# HeadSheet.net
KiCad netlist of a schematic drawn in Altium Designer
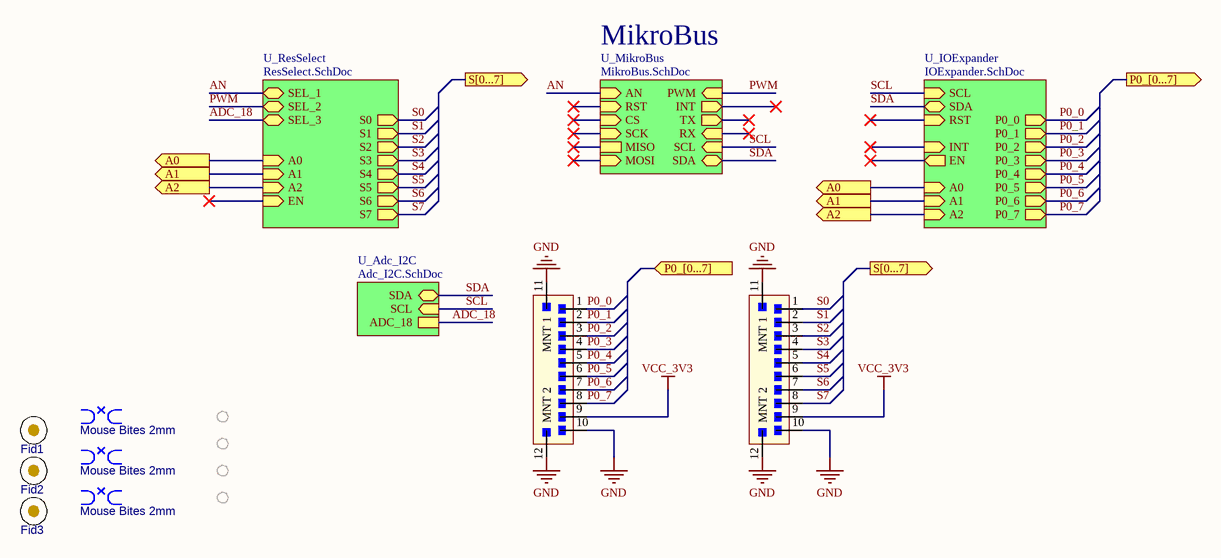
[diagram p0: HeadSheet.SchDoc]

(export (version "E")
  (design (tool "Eeschema 10.0.6"))
  (components
    (comp (ref "BRK1")
      (value "Mouse Bites 2mm")
      (footprint "BK_CRACK1B_M")
      (description "Mouse Bites")
      (fields (field (name "Comment") "DNP"))
      (libsource (lib "TEP-AltiumLib-Hardware") (part "BK_BREAKOUT_2MM"))
    )
    (comp (ref "BRK2")
      (value "Mouse Bites 2mm")
      (footprint "BK_CRACK1B_M")
      (description "Mouse Bites")
      (fields (field (name "Comment") "DNP"))
      (libsource (lib "TEP-AltiumLib-Hardware") (part "BK_BREAKOUT_2MM"))
    )
    (comp (ref "BRK3")
      (value "Mouse Bites 2mm")
      (footprint "BK_CRACK1B_M")
      (description "Mouse Bites")
      (fields (field (name "Comment") "DNP"))
      (libsource (lib "TEP-AltiumLib-Hardware") (part "BK_BREAKOUT_2MM"))
    )
    (comp (ref "Fid1")
      (value "DNP")
      (footprint "FD_Fiducial")
      (description "Fiducial mark for alignement and Pick&Place")
      (libsource (lib "TEP-AltiumLib-Hardware") (part "Fiducial"))
    )
    (comp (ref "Fid2")
      (value "DNP")
      (footprint "FD_Fiducial")
      (description "Fiducial mark for alignement and Pick&Place")
      (libsource (lib "TEP-AltiumLib-Hardware") (part "Fiducial"))
    )
    (comp (ref "Fid3")
      (value "DNP")
      (footprint "FD_Fiducial")
      (description "Fiducial mark for alignement and Pick&Place")
      (libsource (lib "TEP-AltiumLib-Hardware") (part "Fiducial"))
    )
    (comp (ref "J1")
      (value "HC-ZH-10PWT")
      (footprint "J_S10B-ZR-SM4")
      (description "CONN wire to board SMT R/A 10POS 1.5mm")
      (libsource (lib "TEP-AltiumLib-Connectors") (part "CONN-1MM5-01X10-S10B-H-SMT"))
    )
    (comp (ref "J2")
      (value "HC-ZH-10PWT")
      (footprint "J_S10B-ZR-SM4")
      (description "CONN wire to board SMT R/A 10POS 1.5mm")
      (libsource (lib "TEP-AltiumLib-Connectors") (part "CONN-1MM5-01X10-S10B-H-SMT"))
    )
    (comp (ref "MH1")
      (value "DNP")
      (footprint "MP_M-Hole_M2-NonPlated")
      (description "Mounting Hole 2mm non plated")
      (libsource (lib "TEP-AltiumLib-Hardware") (part "MH-2MM_NP"))
    )
    (comp (ref "MH2")
      (value "DNP")
      (footprint "MP_M-Hole_M2-NonPlated")
      (description "Mounting Hole 2mm non plated")
      (libsource (lib "TEP-AltiumLib-Hardware") (part "MH-2MM_NP"))
    )
    (comp (ref "MH3")
      (value "DNP")
      (footprint "MP_M-Hole_M2-NonPlated")
      (description "Mounting Hole 2mm non plated")
      (libsource (lib "TEP-AltiumLib-Hardware") (part "MH-2MM_NP"))
    )
    (comp (ref "MH4")
      (value "DNP")
      (footprint "MP_M-Hole_M2-NonPlated")
      (description "Mounting Hole 2mm non plated")
      (libsource (lib "TEP-AltiumLib-Hardware") (part "MH-2MM_NP"))
    )
  )
  (nets
    (net (code "14") (name "/P0_0") (class "Default")
      (node (ref "J1") (pin "1") (pinfunction "1_1") (pintype "passive"))
    )
    (net (code "15") (name "/P0_1") (class "Default")
      (node (ref "J1") (pin "2") (pinfunction "2_2") (pintype "passive"))
    )
    (net (code "16") (name "/P0_2") (class "Default")
      (node (ref "J1") (pin "3") (pinfunction "3_3") (pintype "passive"))
    )
    (net (code "17") (name "/P0_3") (class "Default")
      (node (ref "J1") (pin "4") (pinfunction "4_4") (pintype "passive"))
    )
    (net (code "18") (name "/P0_4") (class "Default")
      (node (ref "J1") (pin "5") (pinfunction "5_5") (pintype "passive"))
    )
    (net (code "19") (name "/P0_5") (class "Default")
      (node (ref "J1") (pin "6") (pinfunction "6_6") (pintype "passive"))
    )
    (net (code "20") (name "/P0_6") (class "Default")
      (node (ref "J1") (pin "7") (pinfunction "7_7") (pintype "passive"))
    )
    (net (code "21") (name "/P0_7") (class "Default")
      (node (ref "J1") (pin "8") (pinfunction "8_8") (pintype "passive"))
    )
    (net (code "26") (name "/S0") (class "Default")
      (node (ref "J2") (pin "1") (pinfunction "1_1") (pintype "passive"))
    )
    (net (code "27") (name "/S1") (class "Default")
      (node (ref "J2") (pin "2") (pinfunction "2_2") (pintype "passive"))
    )
    (net (code "28") (name "/S2") (class "Default")
      (node (ref "J2") (pin "3") (pinfunction "3_3") (pintype "passive"))
    )
    (net (code "29") (name "/S3") (class "Default")
      (node (ref "J2") (pin "4") (pinfunction "4_4") (pintype "passive"))
    )
    (net (code "30") (name "/S4") (class "Default")
      (node (ref "J2") (pin "5") (pinfunction "5_5") (pintype "passive"))
    )
    (net (code "31") (name "/S5") (class "Default")
      (node (ref "J2") (pin "6") (pinfunction "6_6") (pintype "passive"))
    )
    (net (code "32") (name "/S6") (class "Default")
      (node (ref "J2") (pin "7") (pinfunction "7_7") (pintype "passive"))
    )
    (net (code "33") (name "/S7") (class "Default")
      (node (ref "J2") (pin "8") (pinfunction "8_8") (pintype "passive"))
    )
    (net (code "39") (name "GND") (class "Default")
      (node (ref "J1") (pin "10") (pinfunction "10_10") (pintype "passive"))
      (node (ref "J1") (pin "11") (pinfunction "MNT_1_11") (pintype "passive"))
      (node (ref "J1") (pin "12") (pinfunction "MNT_2_12") (pintype "passive"))
      (node (ref "J2") (pin "10") (pinfunction "10_10") (pintype "passive"))
      (node (ref "J2") (pin "11") (pinfunction "MNT_1_11") (pintype "passive"))
      (node (ref "J2") (pin "12") (pinfunction "MNT_2_12") (pintype "passive"))
    )
    (net (code "40") (name "VCC_3V3") (class "Default")
      (node (ref "J1") (pin "9") (pinfunction "9_9") (pintype "passive"))
      (node (ref "J2") (pin "9") (pinfunction "9_9") (pintype "passive"))
    )
    (net (code "41") (name "unconnected-(BRK1-Pad1)") (class "Default")
      (node (ref "BRK1") (pin "1") (pinfunction "1_1") (pintype "passive"))
    )
    (net (code "42") (name "unconnected-(BRK1-Pad2)") (class "Default")
      (node (ref "BRK1") (pin "2") (pinfunction "2_2") (pintype "passive"))
    )
    (net (code "43") (name "unconnected-(BRK1-Pad3)") (class "Default")
      (node (ref "BRK1") (pin "3") (pinfunction "3_3") (pintype "passive"))
    )
    (net (code "44") (name "unconnected-(BRK1-Pad4)") (class "Default")
      (node (ref "BRK1") (pin "4") (pinfunction "4_4") (pintype "passive"))
    )
    (net (code "45") (name "unconnected-(BRK1-Pad5)") (class "Default")
      (node (ref "BRK1") (pin "5") (pinfunction "5_5") (pintype "passive"))
    )
    (net (code "46") (name "unconnected-(BRK2-Pad1)") (class "Default")
      (node (ref "BRK2") (pin "1") (pinfunction "1_1") (pintype "passive"))
    )
    (net (code "47") (name "unconnected-(BRK2-Pad2)") (class "Default")
      (node (ref "BRK2") (pin "2") (pinfunction "2_2") (pintype "passive"))
    )
    (net (code "48") (name "unconnected-(BRK2-Pad3)") (class "Default")
      (node (ref "BRK2") (pin "3") (pinfunction "3_3") (pintype "passive"))
    )
    (net (code "49") (name "unconnected-(BRK2-Pad4)") (class "Default")
      (node (ref "BRK2") (pin "4") (pinfunction "4_4") (pintype "passive"))
    )
    (net (code "50") (name "unconnected-(BRK2-Pad5)") (class "Default")
      (node (ref "BRK2") (pin "5") (pinfunction "5_5") (pintype "passive"))
    )
    (net (code "51") (name "unconnected-(BRK3-Pad1)") (class "Default")
      (node (ref "BRK3") (pin "1") (pinfunction "1_1") (pintype "passive"))
    )
    (net (code "52") (name "unconnected-(BRK3-Pad2)") (class "Default")
      (node (ref "BRK3") (pin "2") (pinfunction "2_2") (pintype "passive"))
    )
    (net (code "53") (name "unconnected-(BRK3-Pad3)") (class "Default")
      (node (ref "BRK3") (pin "3") (pinfunction "3_3") (pintype "passive"))
    )
    (net (code "54") (name "unconnected-(BRK3-Pad4)") (class "Default")
      (node (ref "BRK3") (pin "4") (pinfunction "4_4") (pintype "passive"))
    )
    (net (code "55") (name "unconnected-(BRK3-Pad5)") (class "Default")
      (node (ref "BRK3") (pin "5") (pinfunction "5_5") (pintype "passive"))
    )
    (net (code "56") (name "unconnected-(Fid1-Pad1)") (class "Default")
      (node (ref "Fid1") (pin "1") (pinfunction "1_1") (pintype "passive"))
    )
    (net (code "57") (name "unconnected-(Fid1-Pad1)_1") (class "Default")
      (node (ref "Fid1") (pin "1") (pinfunction "1_1") (pintype "passive"))
    )
    (net (code "58") (name "unconnected-(Fid1-Pad2)") (class "Default")
      (node (ref "Fid1") (pin "2") (pinfunction "2_2") (pintype "passive"))
    )
    (net (code "59") (name "unconnected-(Fid1-Pad3)") (class "Default")
      (node (ref "Fid1") (pin "3") (pinfunction "3_3") (pintype "passive"))
    )
    (net (code "60") (name "unconnected-(Fid1-Pad4)") (class "Default")
      (node (ref "Fid1") (pin "4") (pinfunction "4_4") (pintype "passive"))
    )
    (net (code "61") (name "unconnected-(Fid1-Pad5)") (class "Default")
      (node (ref "Fid1") (pin "5") (pinfunction "5_5") (pintype "passive"))
    )
    (net (code "62") (name "unconnected-(Fid2-Pad1)") (class "Default")
      (node (ref "Fid2") (pin "1") (pinfunction "1_1") (pintype "passive"))
    )
    (net (code "63") (name "unconnected-(Fid2-Pad1)_1") (class "Default")
      (node (ref "Fid2") (pin "1") (pinfunction "1_1") (pintype "passive"))
    )
    (net (code "64") (name "unconnected-(Fid2-Pad2)") (class "Default")
      (node (ref "Fid2") (pin "2") (pinfunction "2_2") (pintype "passive"))
    )
    (net (code "65") (name "unconnected-(Fid2-Pad3)") (class "Default")
      (node (ref "Fid2") (pin "3") (pinfunction "3_3") (pintype "passive"))
    )
    (net (code "66") (name "unconnected-(Fid2-Pad4)") (class "Default")
      (node (ref "Fid2") (pin "4") (pinfunction "4_4") (pintype "passive"))
    )
    (net (code "67") (name "unconnected-(Fid2-Pad5)") (class "Default")
      (node (ref "Fid2") (pin "5") (pinfunction "5_5") (pintype "passive"))
    )
    (net (code "68") (name "unconnected-(Fid3-Pad1)") (class "Default")
      (node (ref "Fid3") (pin "1") (pinfunction "1_1") (pintype "passive"))
    )
    (net (code "69") (name "unconnected-(Fid3-Pad1)_1") (class "Default")
      (node (ref "Fid3") (pin "1") (pinfunction "1_1") (pintype "passive"))
    )
    (net (code "70") (name "unconnected-(Fid3-Pad2)") (class "Default")
      (node (ref "Fid3") (pin "2") (pinfunction "2_2") (pintype "passive"))
    )
    (net (code "71") (name "unconnected-(Fid3-Pad3)") (class "Default")
      (node (ref "Fid3") (pin "3") (pinfunction "3_3") (pintype "passive"))
    )
    (net (code "72") (name "unconnected-(Fid3-Pad4)") (class "Default")
      (node (ref "Fid3") (pin "4") (pinfunction "4_4") (pintype "passive"))
    )
    (net (code "73") (name "unconnected-(Fid3-Pad5)") (class "Default")
      (node (ref "Fid3") (pin "5") (pinfunction "5_5") (pintype "passive"))
    )
  )
)
